# Spartan6-IO01.net
KiCad netlist of a schematic drawn in Altium Designer
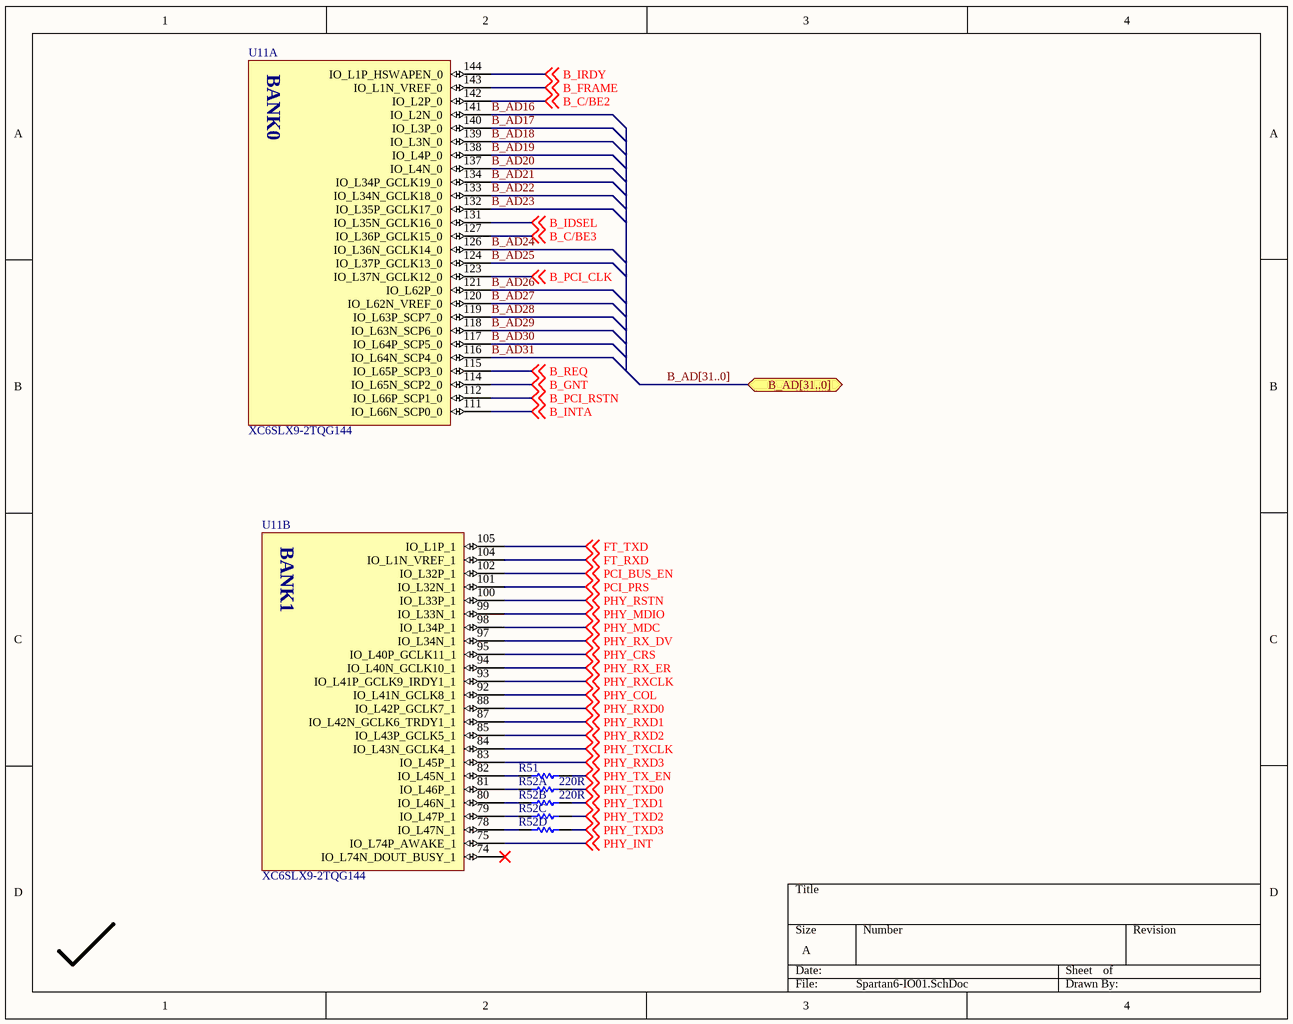
[diagram p0: Spartan6-IO01.SchDoc]

(export (version "E")
  (design (tool "Eeschema 10.0.6"))
  (components
    (comp (ref "R51")
      (value "220R")
      (footprint "0603PKG")
      (description "Semiconductor Resistor")
      (fields (field (name "Comment") "Res Semi") (field (name "PUBLISHER") "Altium Limited"))
      (libsource (lib "Miscellaneous Devices") (part "Res Semi"))
    )
    (comp (ref "R52")
      (value "220R")
      (footprint "ARA4x0603")
      (fields (field (name "Comment") "ChipArray_4x"))
      (libsource (lib "Connector_IntLib") (part "ChipArray_4x"))
    )
    (comp (ref "U11")
      (value "XC6SLX9-2TQG144")
      (footprint "TQG144")
      (description "Xilinx Spartan6 LX9")
      (libsource (lib "Connector_IntLib") (part "XC6SLX9-2TQG144C"))
    )
  )
  (nets
    (net (code "17") (name "/B_AD16") (class "Default")
      (node (ref "U11") (pin "141") (pinfunction "IO_L2N_0_141") (pintype "bidirectional"))
    )
    (net (code "18") (name "/B_AD17") (class "Default")
      (node (ref "U11") (pin "140") (pinfunction "IO_L3P_0_140") (pintype "bidirectional"))
    )
    (net (code "19") (name "/B_AD18") (class "Default")
      (node (ref "U11") (pin "139") (pinfunction "IO_L3N_0_139") (pintype "bidirectional"))
    )
    (net (code "20") (name "/B_AD19") (class "Default")
      (node (ref "U11") (pin "138") (pinfunction "IO_L4P_0_138") (pintype "bidirectional"))
    )
    (net (code "21") (name "/B_AD20") (class "Default")
      (node (ref "U11") (pin "137") (pinfunction "IO_L4N_0_137") (pintype "bidirectional"))
    )
    (net (code "22") (name "/B_AD21") (class "Default")
      (node (ref "U11") (pin "134") (pinfunction "IO_L34P_GCLK19_0_134") (pintype "bidirectional"))
    )
    (net (code "23") (name "/B_AD22") (class "Default")
      (node (ref "U11") (pin "133") (pinfunction "IO_L34N_GCLK18_0_133") (pintype "bidirectional"))
    )
    (net (code "24") (name "/B_AD23") (class "Default")
      (node (ref "U11") (pin "132") (pinfunction "IO_L35P_GCLK17_0_132") (pintype "bidirectional"))
    )
    (net (code "25") (name "/B_AD24") (class "Default")
      (node (ref "U11") (pin "126") (pinfunction "IO_L36N_GCLK14_0_126") (pintype "bidirectional"))
    )
    (net (code "26") (name "/B_AD25") (class "Default")
      (node (ref "U11") (pin "124") (pinfunction "IO_L37P_GCLK13_0_124") (pintype "bidirectional"))
    )
    (net (code "27") (name "/B_AD26") (class "Default")
      (node (ref "U11") (pin "121") (pinfunction "IO_L62P_0_121") (pintype "bidirectional"))
    )
    (net (code "28") (name "/B_AD27") (class "Default")
      (node (ref "U11") (pin "120") (pinfunction "IO_L62N_VREF_0_120") (pintype "bidirectional"))
    )
    (net (code "29") (name "/B_AD28") (class "Default")
      (node (ref "U11") (pin "119") (pinfunction "IO_L63P_SCP7_0_119") (pintype "bidirectional"))
    )
    (net (code "30") (name "/B_AD29") (class "Default")
      (node (ref "U11") (pin "118") (pinfunction "IO_L63N_SCP6_0_118") (pintype "bidirectional"))
    )
    (net (code "31") (name "/B_AD30") (class "Default")
      (node (ref "U11") (pin "117") (pinfunction "IO_L64P_SCP5_0_117") (pintype "bidirectional"))
    )
    (net (code "32") (name "/B_AD31") (class "Default")
      (node (ref "U11") (pin "116") (pinfunction "IO_L64N_SCP4_0_116") (pintype "bidirectional"))
    )
    (net (code "34") (name "B_C{slash}BE2") (class "Default")
      (node (ref "U11") (pin "142") (pinfunction "IO_L2P_0_142") (pintype "bidirectional"))
    )
    (net (code "35") (name "B_C{slash}BE3") (class "Default")
      (node (ref "U11") (pin "127") (pinfunction "IO_L36P_GCLK15_0_127") (pintype "bidirectional"))
    )
    (net (code "36") (name "B_FRAME") (class "Default")
      (node (ref "U11") (pin "143") (pinfunction "IO_L1N_VREF_0_143") (pintype "bidirectional"))
    )
    (net (code "37") (name "B_GNT") (class "Default")
      (node (ref "U11") (pin "114") (pinfunction "IO_L65N_SCP2_0_114") (pintype "bidirectional"))
    )
    (net (code "38") (name "B_IDSEL") (class "Default")
      (node (ref "U11") (pin "131") (pinfunction "IO_L35N_GCLK16_0_131") (pintype "bidirectional"))
    )
    (net (code "39") (name "B_INTA") (class "Default")
      (node (ref "U11") (pin "111") (pinfunction "IO_L66N_SCP0_0_111") (pintype "bidirectional"))
    )
    (net (code "40") (name "B_IRDY") (class "Default")
      (node (ref "U11") (pin "144") (pinfunction "IO_L1P_HSWAPEN_0_144") (pintype "bidirectional"))
    )
    (net (code "41") (name "B_PCI_CLK") (class "Default")
      (node (ref "U11") (pin "123") (pinfunction "IO_L37N_GCLK12_0_123") (pintype "bidirectional"))
    )
    (net (code "42") (name "B_PCI_RSTN") (class "Default")
      (node (ref "U11") (pin "112") (pinfunction "IO_L66P_SCP1_0_112") (pintype "bidirectional"))
    )
    (net (code "43") (name "B_REQ") (class "Default")
      (node (ref "U11") (pin "115") (pinfunction "IO_L65P_SCP3_0_115") (pintype "bidirectional"))
    )
    (net (code "44") (name "FT_RXD") (class "Default")
      (node (ref "U11") (pin "104") (pinfunction "IO_L1N_VREF_1_104") (pintype "bidirectional"))
    )
    (net (code "45") (name "FT_TXD") (class "Default")
      (node (ref "U11") (pin "105") (pinfunction "IO_L1P_1_105") (pintype "bidirectional"))
    )
    (net (code "46") (name "Net-(U11B-IO_L45N_1)") (class "Default")
      (node (ref "R51") (pin "1") (pinfunction "1_1") (pintype "passive"))
      (node (ref "U11") (pin "82") (pinfunction "IO_L45N_1_82") (pintype "bidirectional"))
    )
    (net (code "47") (name "Net-(U11B-IO_L46N_1)") (class "Default")
      (node (ref "R52") (pin "2") (pinfunction "R2_2") (pintype "passive"))
      (node (ref "U11") (pin "80") (pinfunction "IO_L46N_1_80") (pintype "bidirectional"))
    )
    (net (code "48") (name "Net-(U11B-IO_L46P_1)") (class "Default")
      (node (ref "R52") (pin "1") (pinfunction "R1_1") (pintype "passive"))
      (node (ref "U11") (pin "81") (pinfunction "IO_L46P_1_81") (pintype "bidirectional"))
    )
    (net (code "49") (name "Net-(U11B-IO_L47N_1)") (class "Default")
      (node (ref "R52") (pin "4") (pinfunction "R4_4") (pintype "passive"))
      (node (ref "U11") (pin "78") (pinfunction "IO_L47N_1_78") (pintype "bidirectional"))
    )
    (net (code "50") (name "Net-(U11B-IO_L47P_1)") (class "Default")
      (node (ref "R52") (pin "3") (pinfunction "R3_3") (pintype "passive"))
      (node (ref "U11") (pin "79") (pinfunction "IO_L47P_1_79") (pintype "bidirectional"))
    )
    (net (code "51") (name "PCI_BUS_EN") (class "Default")
      (node (ref "U11") (pin "102") (pinfunction "IO_L32P_1_102") (pintype "bidirectional"))
    )
    (net (code "52") (name "PCI_PRS") (class "Default")
      (node (ref "U11") (pin "101") (pinfunction "IO_L32N_1_101") (pintype "bidirectional"))
    )
    (net (code "53") (name "PHY_COL") (class "Default")
      (node (ref "U11") (pin "92") (pinfunction "IO_L41N_GCLK8_1_92") (pintype "bidirectional"))
    )
    (net (code "54") (name "PHY_CRS") (class "Default")
      (node (ref "U11") (pin "95") (pinfunction "IO_L40P_GCLK11_1_95") (pintype "bidirectional"))
    )
    (net (code "55") (name "PHY_INT") (class "Default")
      (node (ref "U11") (pin "75") (pinfunction "IO_L74P_AWAKE_1_75") (pintype "bidirectional"))
    )
    (net (code "56") (name "PHY_MDC") (class "Default")
      (node (ref "U11") (pin "98") (pinfunction "IO_L34P_1_98") (pintype "bidirectional"))
    )
    (net (code "57") (name "PHY_MDIO") (class "Default")
      (node (ref "U11") (pin "99") (pinfunction "IO_L33N_1_99") (pintype "bidirectional"))
    )
    (net (code "58") (name "PHY_RSTN") (class "Default")
      (node (ref "U11") (pin "100") (pinfunction "IO_L33P_1_100") (pintype "bidirectional"))
    )
    (net (code "59") (name "PHY_RXCLK") (class "Default")
      (node (ref "U11") (pin "93") (pinfunction "IO_L41P_GCLK9_IRDY1_1_93") (pintype "bidirectional"))
    )
    (net (code "60") (name "PHY_RXD0") (class "Default")
      (node (ref "U11") (pin "88") (pinfunction "IO_L42P_GCLK7_1_88") (pintype "bidirectional"))
    )
    (net (code "61") (name "PHY_RXD1") (class "Default")
      (node (ref "U11") (pin "87") (pinfunction "IO_L42N_GCLK6_TRDY1_1_87") (pintype "bidirectional"))
    )
    (net (code "62") (name "PHY_RXD2") (class "Default")
      (node (ref "U11") (pin "85") (pinfunction "IO_L43P_GCLK5_1_85") (pintype "bidirectional"))
    )
    (net (code "63") (name "PHY_RXD3") (class "Default")
      (node (ref "U11") (pin "83") (pinfunction "IO_L45P_1_83") (pintype "bidirectional"))
    )
    (net (code "64") (name "PHY_RX_DV") (class "Default")
      (node (ref "U11") (pin "97") (pinfunction "IO_L34N_1_97") (pintype "bidirectional"))
    )
    (net (code "65") (name "PHY_RX_ER") (class "Default")
      (node (ref "U11") (pin "94") (pinfunction "IO_L40N_GCLK10_1_94") (pintype "bidirectional"))
    )
    (net (code "66") (name "PHY_TXCLK") (class "Default")
      (node (ref "U11") (pin "84") (pinfunction "IO_L43N_GCLK4_1_84") (pintype "bidirectional"))
    )
    (net (code "67") (name "PHY_TXD0") (class "Default")
      (node (ref "R52") (pin "8") (pinfunction "R1_8") (pintype "passive"))
    )
    (net (code "68") (name "PHY_TXD1") (class "Default")
      (node (ref "R52") (pin "7") (pinfunction "R2_7") (pintype "passive"))
    )
    (net (code "69") (name "PHY_TXD2") (class "Default")
      (node (ref "R52") (pin "6") (pinfunction "R3_6") (pintype "passive"))
    )
    (net (code "70") (name "PHY_TXD3") (class "Default")
      (node (ref "R52") (pin "5") (pinfunction "R4_5") (pintype "passive"))
    )
    (net (code "71") (name "PHY_TX_EN") (class "Default")
      (node (ref "R51") (pin "2") (pinfunction "2_2") (pintype "passive"))
    )
    (net (code "72") (name "unconnected-(U11B-IO_L74N_DOUT_BUSY_1-Pad74)") (class "Default")
      (node (ref "U11") (pin "74") (pinfunction "IO_L74N_DOUT_BUSY_1_74") (pintype "bidirectional+no_connect"))
    )
  )
)
